# SHIFFTER_BOARD.net
KiCad netlist of a schematic drawn in EAGLE
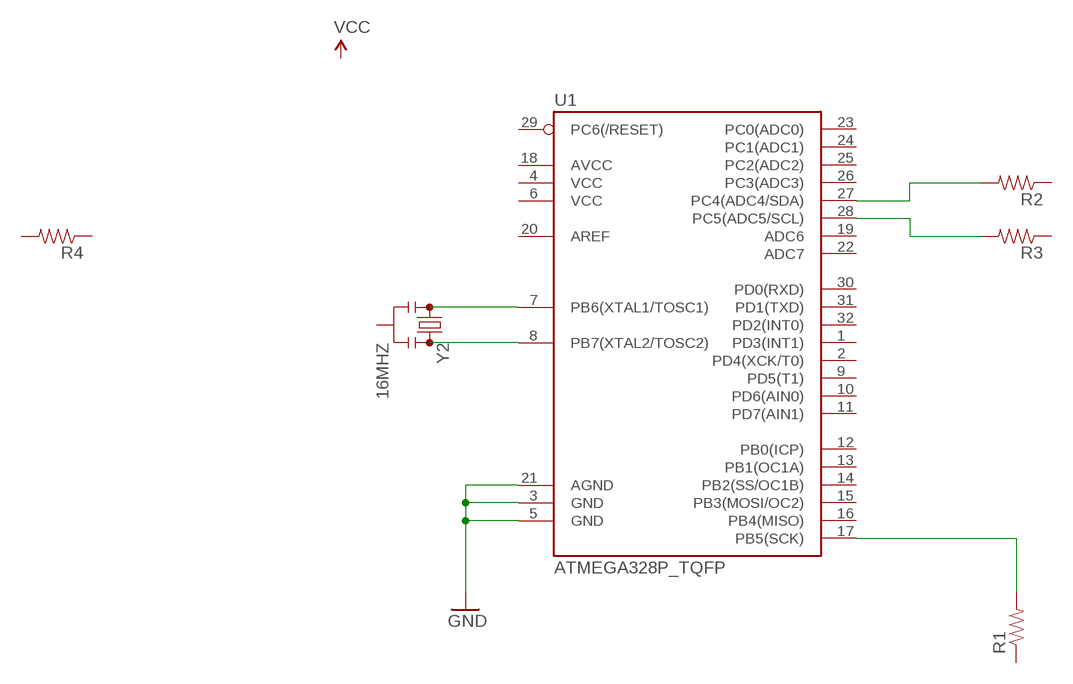
[diagram p0: schematic, sheet 1]

(export (version "E")
  (design (tool "Eeschema 10.0.6"))
  (components
    (comp (ref "R1")
      (value "RESISTOR0805-RES")
      (footprint "eagle-import:0805")
      (libsource (lib "eagle-import") (part "RESISTOR0805-RES"))
    )
    (comp (ref "R2")
      (value "RESISTOR0805-RES")
      (footprint "eagle-import:0805")
      (libsource (lib "eagle-import") (part "RESISTOR0805-RES"))
    )
    (comp (ref "R3")
      (value "RESISTOR0805-RES")
      (footprint "eagle-import:0805")
      (libsource (lib "eagle-import") (part "RESISTOR0805-RES"))
    )
    (comp (ref "R4")
      (value "RESISTOR0805-RES")
      (footprint "eagle-import:0805")
      (libsource (lib "eagle-import") (part "RESISTOR0805-RES"))
    )
    (comp (ref "U1")
      (value "ATMEGA328P_TQFP")
      (footprint "eagle-import:TQFP32-08")
      (libsource (lib "eagle-import") (part "ATMEGA328P_TQFP"))
    )
    (comp (ref "Y2")
      (value "16MHZ")
      (footprint "eagle-import:RESONATOR-SMD")
      (libsource (lib "eagle-import") (part "RESONATOR16MHZ"))
    )
  )
  (nets
    (net (code "1") (name "GND") (class "Default")
      (node (ref "U1") (pin "21") (pinfunction "AGND_21") (pintype "bidirectional"))
      (node (ref "U1") (pin "3") (pinfunction "GND_3") (pintype "bidirectional"))
      (node (ref "U1") (pin "5") (pinfunction "GND_5") (pintype "bidirectional"))
    )
    (net (code "2") (name "Net-(U1-PB5(SCK))") (class "Default")
      (node (ref "R1") (pin "2") (pinfunction "2_2") (pintype "passive"))
      (node (ref "U1") (pin "17") (pinfunction "PB5(SCK)_17") (pintype "bidirectional"))
    )
    (net (code "3") (name "Net-(U1-PB6(XTAL1{slash}TOSC1))") (class "Default")
      (node (ref "U1") (pin "7") (pinfunction "PB6(XTAL1/TOSC1)_7") (pintype "bidirectional"))
      (node (ref "Y2") (pin "1") (pinfunction "1_1") (pintype "passive"))
    )
    (net (code "4") (name "Net-(U1-PB7(XTAL2{slash}TOSC2))") (class "Default")
      (node (ref "U1") (pin "8") (pinfunction "PB7(XTAL2/TOSC2)_8") (pintype "bidirectional"))
      (node (ref "Y2") (pin "3") (pinfunction "3_3") (pintype "passive"))
    )
    (net (code "5") (name "Net-(U1-PC4(ADC4{slash}SDA))") (class "Default")
      (node (ref "R2") (pin "2") (pinfunction "2_2") (pintype "passive"))
      (node (ref "U1") (pin "27") (pinfunction "PC4(ADC4/SDA)_27") (pintype "bidirectional"))
    )
    (net (code "6") (name "Net-(U1-PC5(ADC5{slash}SCL))") (class "Default")
      (node (ref "R3") (pin "2") (pinfunction "2_2") (pintype "passive"))
      (node (ref "U1") (pin "28") (pinfunction "PC5(ADC5/SCL)_28") (pintype "bidirectional"))
    )
    (net (code "8") (name "unconnected-(R1-Pad1)") (class "Default")
      (node (ref "R1") (pin "1") (pinfunction "1_1") (pintype "passive"))
    )
    (net (code "9") (name "unconnected-(R2-Pad1)") (class "Default")
      (node (ref "R2") (pin "1") (pinfunction "1_1") (pintype "passive"))
    )
    (net (code "10") (name "unconnected-(R3-Pad1)") (class "Default")
      (node (ref "R3") (pin "1") (pinfunction "1_1") (pintype "passive"))
    )
    (net (code "11") (name "unconnected-(R4-Pad1)") (class "Default")
      (node (ref "R4") (pin "1") (pinfunction "1_1") (pintype "passive"))
    )
    (net (code "12") (name "unconnected-(R4-Pad2)") (class "Default")
      (node (ref "R4") (pin "2") (pinfunction "2_2") (pintype "passive"))
    )
    (net (code "13") (name "unconnected-(U1-ADC6-Pad19)") (class "Default")
      (node (ref "U1") (pin "19") (pinfunction "ADC6_19") (pintype "bidirectional"))
    )
    (net (code "14") (name "unconnected-(U1-ADC7-Pad22)") (class "Default")
      (node (ref "U1") (pin "22") (pinfunction "ADC7_22") (pintype "bidirectional"))
    )
    (net (code "15") (name "unconnected-(U1-AREF-Pad20)") (class "Default")
      (node (ref "U1") (pin "20") (pinfunction "AREF_20") (pintype "bidirectional"))
    )
    (net (code "16") (name "unconnected-(U1-AVCC-Pad18)") (class "Default")
      (node (ref "U1") (pin "18") (pinfunction "AVCC_18") (pintype "bidirectional"))
    )
    (net (code "17") (name "unconnected-(U1-PB0(ICP)-Pad12)") (class "Default")
      (node (ref "U1") (pin "12") (pinfunction "PB0(ICP)_12") (pintype "bidirectional"))
    )
    (net (code "18") (name "unconnected-(U1-PB1(OC1A)-Pad13)") (class "Default")
      (node (ref "U1") (pin "13") (pinfunction "PB1(OC1A)_13") (pintype "bidirectional"))
    )
    (net (code "19") (name "unconnected-(U1-PB2(SS{slash}OC1B)-Pad14)") (class "Default")
      (node (ref "U1") (pin "14") (pinfunction "PB2(SS/OC1B)_14") (pintype "bidirectional"))
    )
    (net (code "20") (name "unconnected-(U1-PB3(MOSI{slash}OC2)-Pad15)") (class "Default")
      (node (ref "U1") (pin "15") (pinfunction "PB3(MOSI/OC2)_15") (pintype "bidirectional"))
    )
    (net (code "21") (name "unconnected-(U1-PB4(MISO)-Pad16)") (class "Default")
      (node (ref "U1") (pin "16") (pinfunction "PB4(MISO)_16") (pintype "bidirectional"))
    )
    (net (code "22") (name "unconnected-(U1-PC0(ADC0)-Pad23)") (class "Default")
      (node (ref "U1") (pin "23") (pinfunction "PC0(ADC0)_23") (pintype "bidirectional"))
    )
    (net (code "23") (name "unconnected-(U1-PC1(ADC1)-Pad24)") (class "Default")
      (node (ref "U1") (pin "24") (pinfunction "PC1(ADC1)_24") (pintype "bidirectional"))
    )
    (net (code "24") (name "unconnected-(U1-PC2(ADC2)-Pad25)") (class "Default")
      (node (ref "U1") (pin "25") (pinfunction "PC2(ADC2)_25") (pintype "bidirectional"))
    )
    (net (code "25") (name "unconnected-(U1-PC3(ADC3)-Pad26)") (class "Default")
      (node (ref "U1") (pin "26") (pinfunction "PC3(ADC3)_26") (pintype "bidirectional"))
    )
    (net (code "26") (name "unconnected-(U1-PC6({slash}RESET)-Pad29)") (class "Default")
      (node (ref "U1") (pin "29") (pinfunction "PC6(/RESET)_29") (pintype "bidirectional"))
    )
    (net (code "27") (name "unconnected-(U1-PD0(RXD)-Pad30)") (class "Default")
      (node (ref "U1") (pin "30") (pinfunction "PD0(RXD)_30") (pintype "bidirectional"))
    )
    (net (code "28") (name "unconnected-(U1-PD1(TXD)-Pad31)") (class "Default")
      (node (ref "U1") (pin "31") (pinfunction "PD1(TXD)_31") (pintype "bidirectional"))
    )
    (net (code "29") (name "unconnected-(U1-PD2(INT0)-Pad32)") (class "Default")
      (node (ref "U1") (pin "32") (pinfunction "PD2(INT0)_32") (pintype "bidirectional"))
    )
    (net (code "30") (name "unconnected-(U1-PD3(INT1)-Pad1)") (class "Default")
      (node (ref "U1") (pin "1") (pinfunction "PD3(INT1)_1") (pintype "bidirectional"))
    )
    (net (code "31") (name "unconnected-(U1-PD4(XCK{slash}T0)-Pad2)") (class "Default")
      (node (ref "U1") (pin "2") (pinfunction "PD4(XCK/T0)_2") (pintype "bidirectional"))
    )
    (net (code "32") (name "unconnected-(U1-PD5(T1)-Pad9)") (class "Default")
      (node (ref "U1") (pin "9") (pinfunction "PD5(T1)_9") (pintype "bidirectional"))
    )
    (net (code "33") (name "unconnected-(U1-PD6(AIN0)-Pad10)") (class "Default")
      (node (ref "U1") (pin "10") (pinfunction "PD6(AIN0)_10") (pintype "bidirectional"))
    )
    (net (code "34") (name "unconnected-(U1-PD7(AIN1)-Pad11)") (class "Default")
      (node (ref "U1") (pin "11") (pinfunction "PD7(AIN1)_11") (pintype "bidirectional"))
    )
    (net (code "35") (name "unconnected-(U1-VCC-Pad4)") (class "Default")
      (node (ref "U1") (pin "4") (pinfunction "VCC_4") (pintype "bidirectional"))
    )
    (net (code "36") (name "unconnected-(U1-VCC-Pad6)") (class "Default")
      (node (ref "U1") (pin "6") (pinfunction "VCC_6") (pintype "bidirectional"))
    )
    (net (code "37") (name "unconnected-(Y2-Pad2)") (class "Default")
      (node (ref "Y2") (pin "2") (pinfunction "2_2") (pintype "passive"))
    )
  )
)
